# 12_-_RTC.net
KiCad netlist of a schematic drawn in Altium Designer
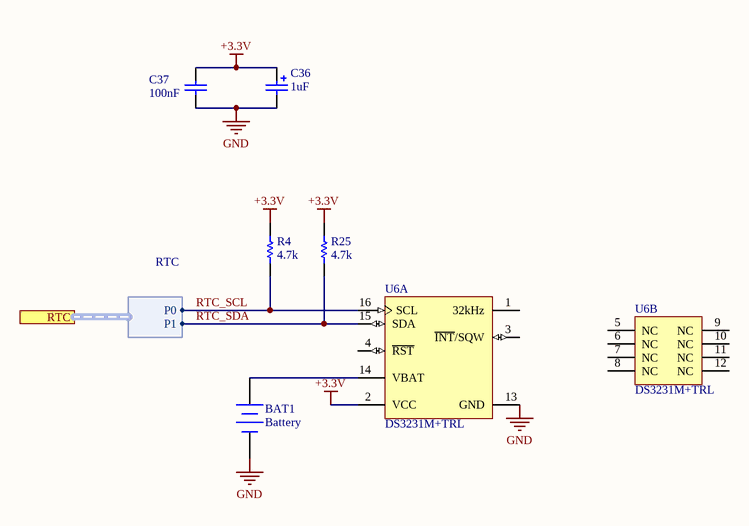
[diagram p0: [12] - RTC.SchDoc]

(export (version "E")
  (design (tool "Eeschema 10.0.6"))
  (components
    (comp (ref "BAT1")
      (value "Battery")
      (footprint "Blue Tractor-2021:Bat")
      (description "Multicell Battery")
      (fields (field (name "PUBLISHER") "Altium Limited"))
      (libsource (lib "Miscellaneous Devices") (part "Battery"))
    )
    (comp (ref "C36")
      (value "Capacitor Polarized")
      (footprint "Tantalum 3216 A")
      (description "Aluminium SMD Capacitors")
      (fields
        (field (name "MANUFACTURER") "Panasonic")
        (field (name "MANUFACTURER PART NUMBER") "EEE-1VA331P")
        (field (name "CAPACITANCE") "1uF")
      )
      (libsource (lib "Altium_Library") (part "Capacitor Polarized"))
    )
    (comp (ref "C37")
      (value "Capacitor")
      (footprint "Blue Tractor-2021:0603_C")
      (description "Chip Capacitor Nonpolar")
      (fields
        (field (name "MANUFACTURER") "Samsung")
        (field (name "MANUFACTURER PART NUMBER") "CL10B104KB8NNNC")
        (field (name "CAPACITANCE") "100nF")
      )
      (libsource (lib "Altium_Library") (part "Capacitor"))
    )
    (comp (ref "R4")
      (value "Res1")
      (footprint "Res-0603")
      (description "Chip Resistor")
      (fields
        (field (name "MANUFACTURER") "Panasonic")
        (field (name "MANUFACTURER PART NUMBER") "ERJ-3GEYJ222V")
        (field (name "RESISTANCE") "4.7k")
      )
      (libsource (lib "Altium_Library") (part "Res1"))
    )
    (comp (ref "R25")
      (value "Res1")
      (footprint "Res-0603")
      (description "Chip Resistor")
      (fields
        (field (name "MANUFACTURER") "Panasonic")
        (field (name "MANUFACTURER PART NUMBER") "ERJ-3GEYJ222V")
        (field (name "RESISTANCE") "4.7k")
      )
      (libsource (lib "Altium_Library") (part "Res1"))
    )
    (comp (ref "U6")
      (value "DS3231M+TRL")
      (footprint "Blue Tractor-2021:DS3231-RTC")
      (description "+/-5ppm, MEMS based Real-Time Clock, I2C Interface, 16-Pin SO, -40 to 85 degC, Pb-Free, Reel")
      (libsource (lib "Blue Tractor-2021") (part "DS3231M-IL16-RTC"))
    )
  )
  (nets
    (net (code "2") (name "+3.3V") (class "Default")
      (node (ref "C36") (pin "1") (pinfunction "1_1") (pintype "passive"))
      (node (ref "C37") (pin "2") (pinfunction "2_2") (pintype "passive"))
      (node (ref "R25") (pin "1") (pinfunction "1_1") (pintype "passive"))
      (node (ref "R4") (pin "1") (pinfunction "1_1") (pintype "passive"))
      (node (ref "U6") (pin "2") (pinfunction "VCC_2") (pintype "power_in"))
    )
    (net (code "3") (name "/RTC_SCL") (class "Default")
      (node (ref "R4") (pin "2") (pinfunction "2_2") (pintype "passive"))
      (node (ref "U6") (pin "16") (pinfunction "SCL_16") (pintype "input"))
    )
    (net (code "4") (name "/RTC_SDA") (class "Default")
      (node (ref "R25") (pin "2") (pinfunction "2_2") (pintype "passive"))
      (node (ref "U6") (pin "15") (pinfunction "SDA_15") (pintype "bidirectional"))
    )
    (net (code "6") (name "GND") (class "Default")
      (node (ref "BAT1") (pin "2") (pinfunction "-_2") (pintype "passive"))
      (node (ref "C36") (pin "2") (pinfunction "2_2") (pintype "passive"))
      (node (ref "C37") (pin "1") (pinfunction "1_1") (pintype "passive"))
      (node (ref "U6") (pin "13") (pinfunction "GND_13") (pintype "power_in"))
    )
    (net (code "7") (name "Net-(BAT1-+)") (class "Default")
      (node (ref "BAT1") (pin "1") (pinfunction "+_1") (pintype "passive"))
      (node (ref "U6") (pin "14") (pinfunction "VBAT_14") (pintype "power_in"))
    )
    (net (code "8") (name "unconnected-(U6A-32kHz-Pad1)") (class "Default")
      (node (ref "U6") (pin "1") (pinfunction "32kHz_1") (pintype "open_collector"))
    )
    (net (code "9") (name "unconnected-(U6A-~{INT}{slash}SQW-Pad3)") (class "Default")
      (node (ref "U6") (pin "3") (pinfunction "~{INT}/SQW_3") (pintype "bidirectional"))
    )
    (net (code "10") (name "unconnected-(U6A-~{RST}-Pad4)") (class "Default")
      (node (ref "U6") (pin "4") (pinfunction "~{RST}_4") (pintype "bidirectional"))
    )
    (net (code "11") (name "unconnected-(U6B-NC-Pad5)") (class "Default")
      (node (ref "U6") (pin "5") (pinfunction "NC_5") (pintype "passive"))
    )
    (net (code "12") (name "unconnected-(U6B-NC-Pad6)") (class "Default")
      (node (ref "U6") (pin "6") (pinfunction "NC_6") (pintype "passive"))
    )
    (net (code "13") (name "unconnected-(U6B-NC-Pad7)") (class "Default")
      (node (ref "U6") (pin "7") (pinfunction "NC_7") (pintype "passive"))
    )
    (net (code "14") (name "unconnected-(U6B-NC-Pad8)") (class "Default")
      (node (ref "U6") (pin "8") (pinfunction "NC_8") (pintype "passive"))
    )
    (net (code "15") (name "unconnected-(U6B-NC-Pad9)") (class "Default")
      (node (ref "U6") (pin "9") (pinfunction "NC_9") (pintype "passive"))
    )
    (net (code "16") (name "unconnected-(U6B-NC-Pad10)") (class "Default")
      (node (ref "U6") (pin "10") (pinfunction "NC_10") (pintype "passive"))
    )
    (net (code "17") (name "unconnected-(U6B-NC-Pad11)") (class "Default")
      (node (ref "U6") (pin "11") (pinfunction "NC_11") (pintype "passive"))
    )
    (net (code "18") (name "unconnected-(U6B-NC-Pad12)") (class "Default")
      (node (ref "U6") (pin "12") (pinfunction "NC_12") (pintype "passive"))
    )
  )
)
